# PCIe_x4.net
KiCad netlist of a schematic drawn in Altium Designer
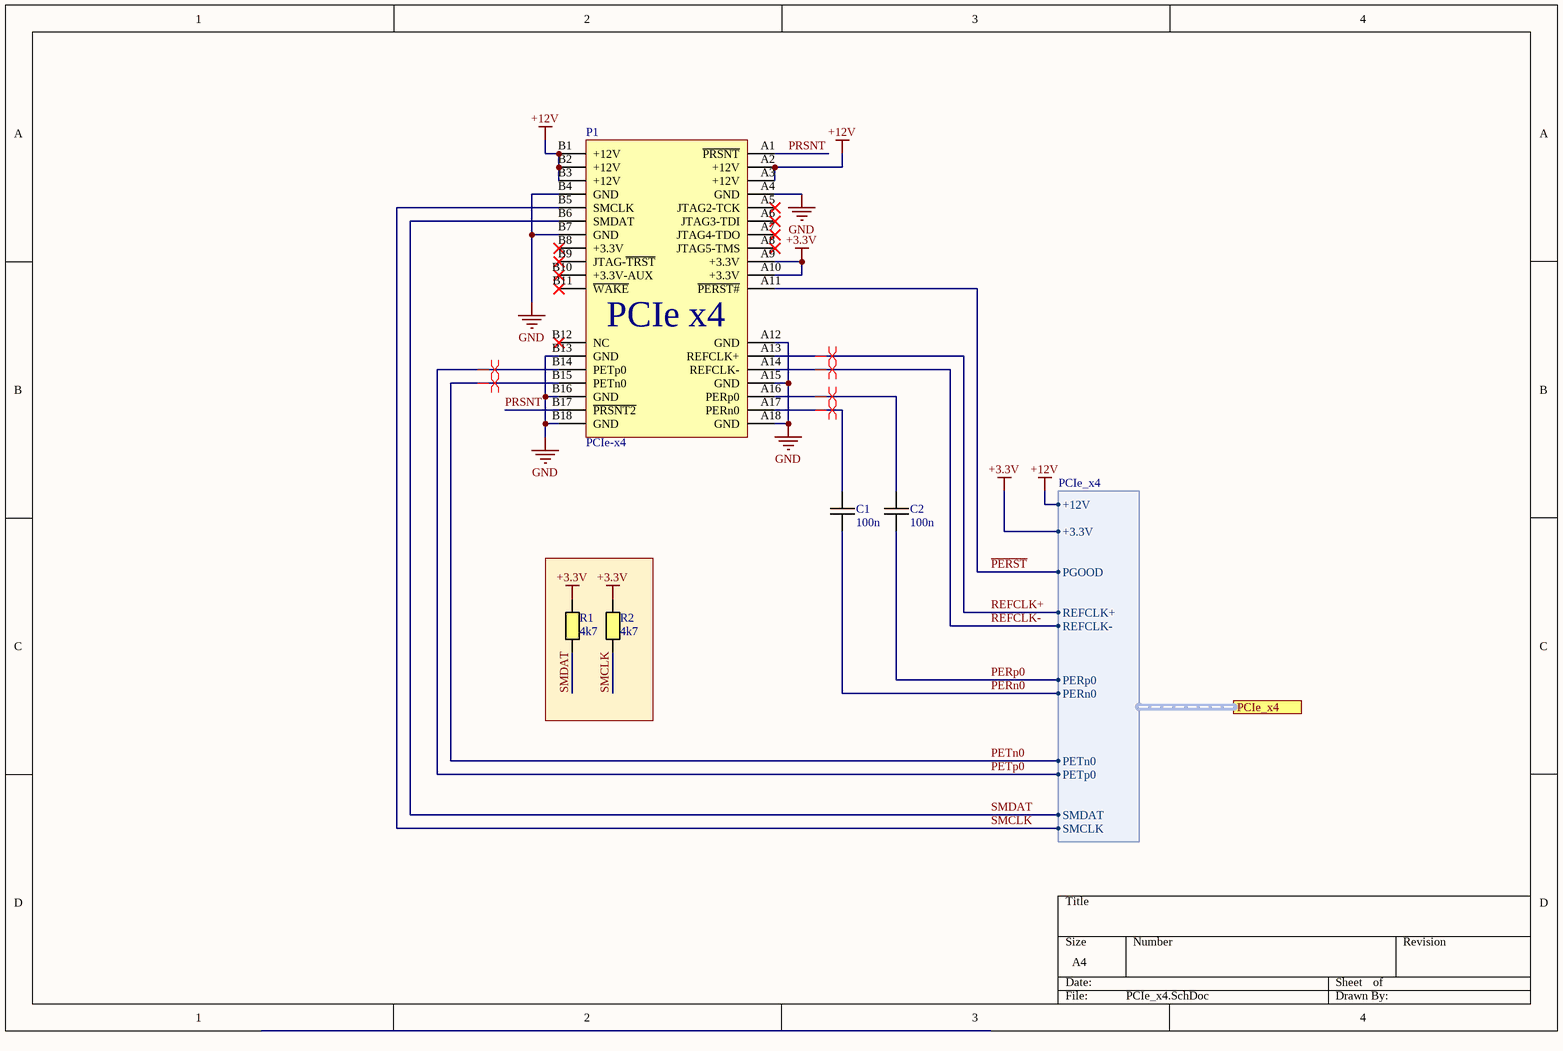
[diagram p0: PCIe_x4.SchDoc]

(export (version "E")
  (design (tool "Eeschema 10.0.6"))
  (components
    (comp (ref "C1")
      (value "100n")
      (footprint "CAPC0603(1608)55_M")
      (description "Ceramic capacitor Low density")
      (libsource (lib "Discrete_Passive_RCL") (part "Capacitor L"))
    )
    (comp (ref "C2")
      (value "100n")
      (footprint "CAPC0603(1608)55_M")
      (description "Ceramic capacitor Low density")
      (libsource (lib "Discrete_Passive_RCL") (part "Capacitor L"))
    )
    (comp (ref "P1")
      (value "PCIe-x4")
      (footprint "PCIe x4 edge connector")
      (libsource (lib "Connectors_DEBUG_Testpoints") (part "PCIe x4"))
    )
    (comp (ref "R1")
      (value "4k7")
      (footprint "RESC1210(3225)_N")
      (description "Resistor Medium Density")
      (libsource (lib "Discrete_Passive_RCL") (part "Resistor M"))
    )
    (comp (ref "R2")
      (value "4k7")
      (footprint "RESC1210(3225)_N")
      (description "Resistor Medium Density")
      (libsource (lib "Discrete_Passive_RCL") (part "Resistor M"))
    )
  )
  (nets
    (net (code "2") (name "+3.3V") (class "Default")
      (node (ref "P1") (pin "A10") (pinfunction "+3.3V_A10") (pintype "passive"))
      (node (ref "P1") (pin "A9") (pinfunction "+3.3V_A9") (pintype "passive"))
      (node (ref "R1") (pin "2") (pinfunction "2_2") (pintype "passive"))
      (node (ref "R2") (pin "2") (pinfunction "2_2") (pintype "passive"))
    )
    (net (code "3") (name "+12V") (class "Default")
      (node (ref "P1") (pin "A2") (pinfunction "+12V_A2") (pintype "passive"))
      (node (ref "P1") (pin "A3") (pinfunction "+12V_A3") (pintype "passive"))
      (node (ref "P1") (pin "B1") (pinfunction "+12V_B1") (pintype "passive"))
      (node (ref "P1") (pin "B2") (pinfunction "+12V_B2") (pintype "passive"))
      (node (ref "P1") (pin "B3") (pinfunction "+12V_B3") (pintype "passive"))
    )
    (net (code "4") (name "/PERn0") (class "Default")
      (node (ref "C1") (pin "2") (pinfunction "2_2") (pintype "passive"))
    )
    (net (code "5") (name "/PERp0") (class "Default")
      (node (ref "C2") (pin "2") (pinfunction "2_2") (pintype "passive"))
    )
    (net (code "6") (name "/PETn0") (class "Default")
      (node (ref "P1") (pin "B15") (pinfunction "PETn0_B15") (pintype "passive"))
    )
    (net (code "7") (name "/PETp0") (class "Default")
      (node (ref "P1") (pin "B14") (pinfunction "PETp0_B14") (pintype "passive"))
    )
    (net (code "8") (name "/PRSNT") (class "Default")
      (node (ref "P1") (pin "A1") (pinfunction "~{PRSNT}_A1") (pintype "passive"))
      (node (ref "P1") (pin "B17") (pinfunction "~{PRSNT2}_B17") (pintype "passive"))
    )
    (net (code "9") (name "/REFCLK+") (class "Default")
      (node (ref "P1") (pin "A13") (pinfunction "REFCLK+_A13") (pintype "passive"))
    )
    (net (code "10") (name "/REFCLK-") (class "Default")
      (node (ref "P1") (pin "A14") (pinfunction "REFCLK-_A14") (pintype "passive"))
    )
    (net (code "11") (name "/SMCLK") (class "Default")
      (node (ref "P1") (pin "B5") (pinfunction "SMCLK_B5") (pintype "passive"))
      (node (ref "R2") (pin "1") (pinfunction "1_1") (pintype "passive"))
    )
    (net (code "12") (name "/SMDAT") (class "Default")
      (node (ref "P1") (pin "B6") (pinfunction "SMDAT_B6") (pintype "passive"))
      (node (ref "R1") (pin "1") (pinfunction "1_1") (pintype "passive"))
    )
    (net (code "14") (name "/~{PERST}") (class "Default")
      (node (ref "P1") (pin "A11") (pinfunction "~{PERST#}_A11") (pintype "passive"))
    )
    (net (code "15") (name "GND") (class "Default")
      (node (ref "P1") (pin "A12") (pinfunction "GND_A12") (pintype "passive"))
      (node (ref "P1") (pin "A15") (pinfunction "GND_A15") (pintype "passive"))
      (node (ref "P1") (pin "A18") (pinfunction "GND_A18") (pintype "passive"))
      (node (ref "P1") (pin "A4") (pinfunction "GND_A4") (pintype "passive"))
      (node (ref "P1") (pin "B13") (pinfunction "GND_B13") (pintype "passive"))
      (node (ref "P1") (pin "B16") (pinfunction "GND_B16") (pintype "passive"))
      (node (ref "P1") (pin "B18") (pinfunction "GND_B18") (pintype "passive"))
      (node (ref "P1") (pin "B4") (pinfunction "GND_B4") (pintype "passive"))
      (node (ref "P1") (pin "B7") (pinfunction "GND_B7") (pintype "passive"))
    )
    (net (code "16") (name "Net-(P1-PERn0)") (class "Default")
      (node (ref "C1") (pin "1") (pinfunction "1_1") (pintype "passive"))
      (node (ref "P1") (pin "A17") (pinfunction "PERn0_A17") (pintype "passive"))
    )
    (net (code "17") (name "Net-(P1-PERp0)") (class "Default")
      (node (ref "C2") (pin "1") (pinfunction "1_1") (pintype "passive"))
      (node (ref "P1") (pin "A16") (pinfunction "PERp0_A16") (pintype "passive"))
    )
    (net (code "18") (name "unconnected-(P1-+3.3V-AUX-PadB10)") (class "Default")
      (node (ref "P1") (pin "B10") (pinfunction "+3.3V-AUX_B10") (pintype "passive+no_connect"))
    )
    (net (code "19") (name "unconnected-(P1-+3.3V-PadB8)") (class "Default")
      (node (ref "P1") (pin "B8") (pinfunction "+3.3V_B8") (pintype "passive+no_connect"))
    )
    (net (code "20") (name "unconnected-(P1-JTAG-~{TRST}-PadB9)") (class "Default")
      (node (ref "P1") (pin "B9") (pinfunction "JTAG-~{TRST}_B9") (pintype "passive+no_connect"))
    )
    (net (code "21") (name "unconnected-(P1-JTAG2-TCK-PadA5)") (class "Default")
      (node (ref "P1") (pin "A5") (pinfunction "JTAG2-TCK_A5") (pintype "passive+no_connect"))
    )
    (net (code "22") (name "unconnected-(P1-JTAG3-TDI-PadA6)") (class "Default")
      (node (ref "P1") (pin "A6") (pinfunction "JTAG3-TDI_A6") (pintype "passive+no_connect"))
    )
    (net (code "23") (name "unconnected-(P1-JTAG4-TDO-PadA7)") (class "Default")
      (node (ref "P1") (pin "A7") (pinfunction "JTAG4-TDO_A7") (pintype "passive+no_connect"))
    )
    (net (code "24") (name "unconnected-(P1-JTAG5-TMS-PadA8)") (class "Default")
      (node (ref "P1") (pin "A8") (pinfunction "JTAG5-TMS_A8") (pintype "passive+no_connect"))
    )
    (net (code "25") (name "unconnected-(P1-NC-PadB12)") (class "Default")
      (node (ref "P1") (pin "B12") (pinfunction "NC_B12") (pintype "passive+no_connect"))
    )
    (net (code "26") (name "unconnected-(P1-~{WAKE}-PadB11)") (class "Default")
      (node (ref "P1") (pin "B11") (pinfunction "~{WAKE}_B11") (pintype "passive+no_connect"))
    )
  )
)
